# PowerSupply.net
KiCad netlist of a schematic drawn in Altium Designer
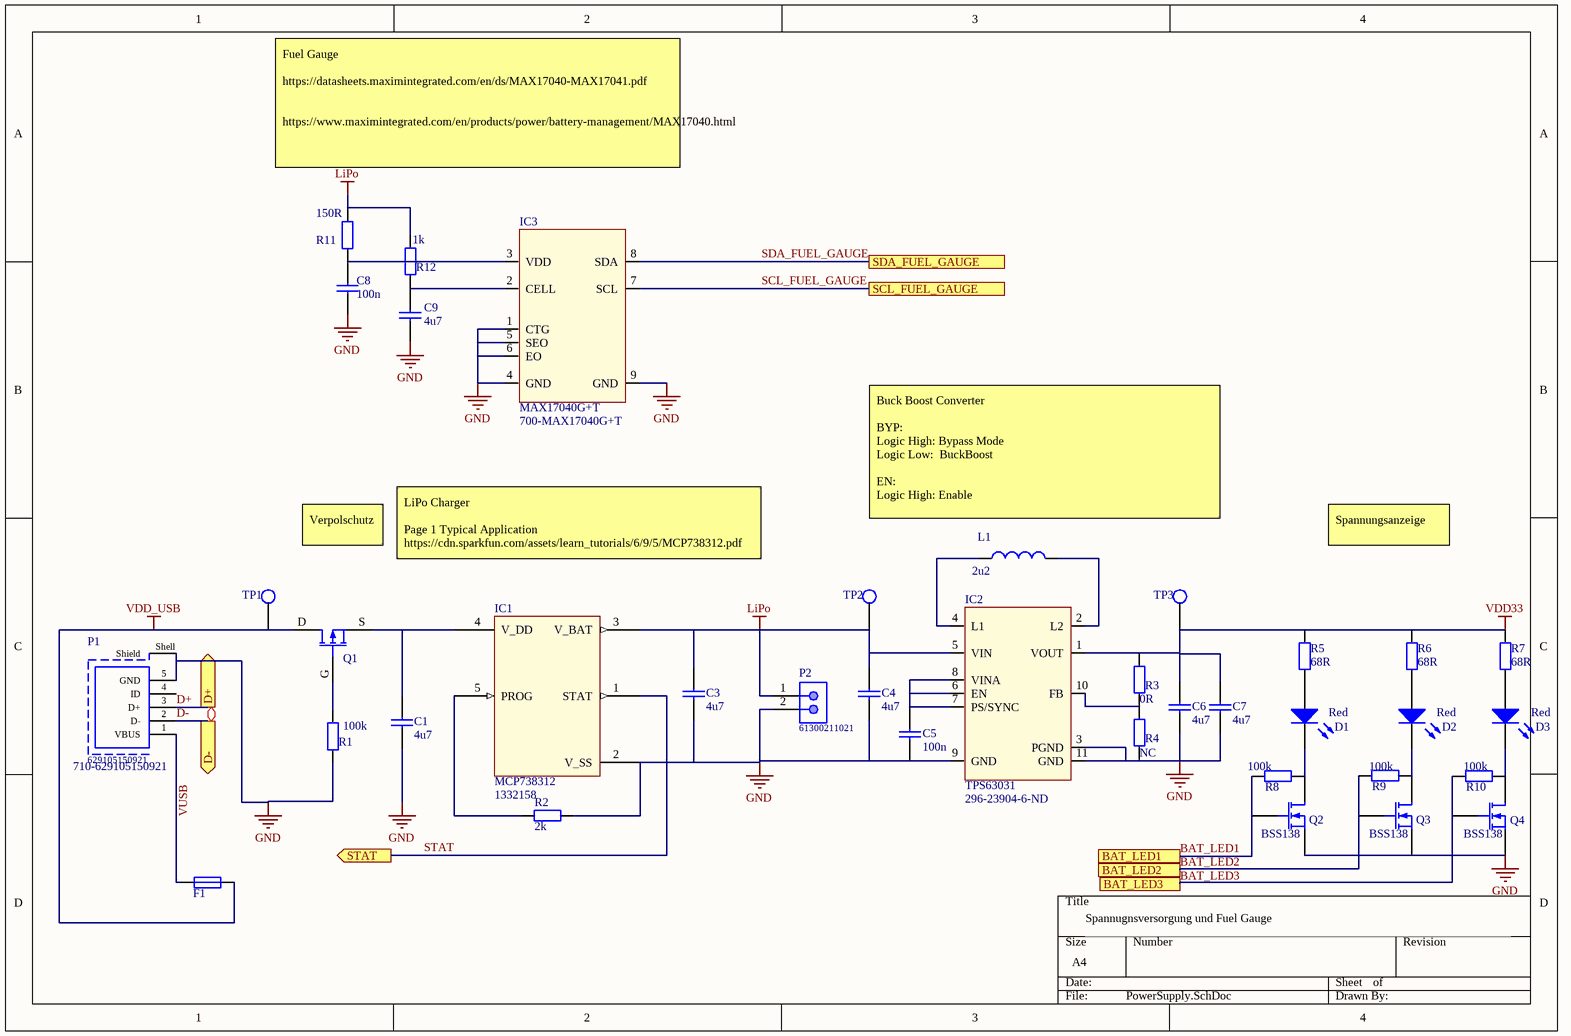
[diagram p0: PowerSupply.SchDoc]

(export (version "E")
  (design (tool "Eeschema 10.0.6"))
  (components
    (comp (ref "C1")
      (value "4u7")
      (footprint "CAPC1005X55")
      (description "Ceramic Chip Capacitor")
      (fields (field (name "MANUFACTURER") "TDK") (field (name "VOLTAGE") "10V"))
      (libsource (lib "SCT_MySQL_5.1") (part "Capacitor"))
    )
    (comp (ref "C3")
      (value "4u7")
      (footprint "CAPC1005X55")
      (description "Ceramic Chip Capacitor")
      (fields (field (name "MANUFACTURER") "Murata") (field (name "VOLTAGE") "6.3V"))
      (libsource (lib "SCT_MySQL_5.1") (part "Capacitor"))
    )
    (comp (ref "C4")
      (value "4u7")
      (footprint "CAPC1005X55")
      (description "Ceramic Chip Capacitor")
      (fields (field (name "MANUFACTURER") "Murata") (field (name "VOLTAGE") "6.3V"))
      (libsource (lib "SCT_MySQL_5.1") (part "Capacitor"))
    )
    (comp (ref "C5")
      (value "100n")
      (footprint "CAPC1005X55")
      (fields
        (field (name "MANUFACTURER") "Kemet")
        (field (name "VOLTAGE") "16V")
        (field (name "TOLERANCE") "±15%")
      )
      (libsource (lib "SCT_MySQL_5.1") (part "Capacitor"))
    )
    (comp (ref "C6")
      (value "4u7")
      (footprint "CAPC1005X55")
      (description "Ceramic Chip Capacitor")
      (fields (field (name "MANUFACTURER") "Murata") (field (name "VOLTAGE") "6.3V"))
      (libsource (lib "SCT_MySQL_5.1") (part "Capacitor"))
    )
    (comp (ref "C7")
      (value "4u7")
      (footprint "CAPC1005X55")
      (description "Ceramic Chip Capacitor")
      (fields (field (name "MANUFACTURER") "Murata") (field (name "VOLTAGE") "6.3V"))
      (libsource (lib "SCT_MySQL_5.1") (part "Capacitor"))
    )
    (comp (ref "C8")
      (value "100n")
      (footprint "CAPC1005X55")
      (description "Ceramic Chip Capacitor")
      (fields (field (name "MANUFACTURER") "Kemet") (field (name "VOLTAGE") "16V"))
      (libsource (lib "SCT_MySQL_5.1") (part "Capacitor"))
    )
    (comp (ref "C9")
      (value "4u7")
      (footprint "CAPC1005X55")
      (description "Ceramic Chip Capacitor")
      (fields (field (name "MANUFACTURER") "TDK") (field (name "VOLTAGE") "10V"))
      (libsource (lib "SCT_MySQL_5.1") (part "Capacitor"))
    )
    (comp (ref "D1")
      (value "Red")
      (footprint "LEDC2012X90")
      (description "SMD Chip LED")
      (fields (field (name "MANUFACTURER") "Avago"))
      (libsource (lib "SCT_MySQL_5.1") (part "LED"))
    )
    (comp (ref "D2")
      (value "Red")
      (footprint "LEDC2012X90")
      (description "SMD Chip LED")
      (fields (field (name "MANUFACTURER") "Avago"))
      (libsource (lib "SCT_MySQL_5.1") (part "LED"))
    )
    (comp (ref "D3")
      (value "Red")
      (footprint "LEDC2012X90")
      (description "SMD Chip LED")
      (fields (field (name "MANUFACTURER") "Avago"))
      (libsource (lib "SCT_MySQL_5.1") (part "LED"))
    )
    (comp (ref "F1")
      (value "~")
      (footprint "RESC3216X65")
      (description "0.5A PTC Fuse")
      (fields (field (name "MANUFACTURER") "POLY-FUSE"))
      (libsource (lib "SCT_MySQL_5.1") (part "Fuse"))
    )
    (comp (ref "IC1")
      (value "MCP738312")
      (footprint "MCP738312")
      (fields (field (name "SUPPLIER PART NUMBER 1") "1332158"))
      (libsource (lib "Lib") (part "MCP738312"))
    )
    (comp (ref "IC2")
      (value "TPS63031")
      (footprint "TPS63031")
      (fields (field (name "SUPPLIER PART NUMBER 1") "296-23904-6-ND"))
      (libsource (lib "Lib") (part "TPS63031"))
    )
    (comp (ref "IC3")
      (value "MAX17040G+T")
      (footprint "MAX17040G+T")
      (fields (field (name "SUPPLIER PART NUMBER 1") "700-MAX17040G+T"))
      (libsource (lib "Lib") (part "MAX17040G+T"))
    )
    (comp (ref "L1")
      (value "2u2")
      (footprint "INDM3030X150")
      (description "SMD Inductor")
      (fields (field (name "MANUFACTURER") "Taiyo Yuden") (field (name "TOLERANCE") "± 20%"))
      (libsource (lib "SCT_MySQL_5.1") (part "Inductor (Coil)"))
    )
    (comp (ref "P1")
      (value "629105150921")
      (footprint "629105150921")
      (description "Micro USB 2.0 Type AB Receptacle WR-COM, Horizontal, SMT")
      (fields
        (field (name "SUPPLIER PART NUMBER 1") "710-629105150921")
        (field (name "PUBLISHER") "Wurth Elektronik")
      )
      (libsource (lib "USB Connectors WR-USB") (part "629105150921"))
    )
    (comp (ref "P2")
      (value "61300211021")
      (footprint "61300211021")
      (description "THT Angled Pin Header WR-PHD, Pitch 2.54 mm, Single Row, 2 pins")
      (fields (field (name "PUBLISHER") "Wurth Elektronik"))
      (libsource (lib "ALTIUM-PHD_2_54_THT_ANGLED_PIN_HEADER_6130XX11021-rev18b (1)") (part "61300211021"))
    )
    (comp (ref "Q1")
      (value "IRLML9301TRPBF")
      (footprint "SOT95P240X130_SGD-3")
      (description "P-channel enhancement mode MOS transistor")
      (fields (field (name "MANUFACTURER") "International Rectifier"))
      (libsource (lib "SCT_MySQL_5.1") (part "MOSFET_P"))
    )
    (comp (ref "Q2")
      (value "BSS138")
      (footprint "SOT95P240X130_SGD-3")
      (description "N-channel enhancement mode MOS transistor")
      (fields (field (name "MANUFACTURER") "Infineon"))
      (libsource (lib "SCT_MySQL_5.1") (part "MOSFET_N"))
    )
    (comp (ref "Q3")
      (value "BSS138")
      (footprint "SOT95P240X130_SGD-3")
      (description "N-channel enhancement mode MOS transistor")
      (fields (field (name "MANUFACTURER") "Infineon"))
      (libsource (lib "SCT_MySQL_5.1") (part "MOSFET_N"))
    )
    (comp (ref "Q4")
      (value "BSS138")
      (footprint "SOT95P240X130_SGD-3")
      (description "N-channel enhancement mode MOS transistor")
      (fields (field (name "MANUFACTURER") "Infineon"))
      (libsource (lib "SCT_MySQL_5.1") (part "MOSFET_N"))
    )
    (comp (ref "R1")
      (value "100k")
      (footprint "RESC1005X40")
      (description "Resistor")
      (fields (field (name "MANUFACTURER") "Multicomp") (field (name "TOLERANCE") "±1%"))
      (libsource (lib "SCT_MySQL_5.1") (part "Resistor"))
    )
    (comp (ref "R2")
      (value "2k")
      (footprint "RESC1005X40")
      (description "Resistor")
      (fields (field (name "MANUFACTURER") "Multicomp") (field (name "TOLERANCE") "±1%"))
      (libsource (lib "") (part "Resistor_2"))
    )
    (comp (ref "R3")
      (value "0R")
      (footprint "RESC1005X40")
      (description "Resistor")
      (fields (field (name "MANUFACTURER") "Multicomp") (field (name "TOLERANCE") "±1%"))
      (libsource (lib "SCT_MySQL_5.1") (part "Resistor"))
    )
    (comp (ref "R4")
      (value "NC")
      (footprint "RESC1005X40")
      (description "Resistor")
      (fields (field (name "MANUFACTURER") "Multicomp") (field (name "TOLERANCE") "±1%"))
      (libsource (lib "SCT_MySQL_5.1") (part "Resistor"))
    )
    (comp (ref "R5")
      (value "68R")
      (footprint "RESC1005X40")
      (description "Resistor")
      (fields (field (name "MANUFACTURER") "Multicomp") (field (name "TOLERANCE") "±1%"))
      (libsource (lib "SCT_MySQL_5.1") (part "Resistor"))
    )
    (comp (ref "R6")
      (value "68R")
      (footprint "RESC1005X40")
      (description "Resistor")
      (fields (field (name "MANUFACTURER") "Multicomp") (field (name "TOLERANCE") "±1%"))
      (libsource (lib "SCT_MySQL_5.1") (part "Resistor"))
    )
    (comp (ref "R7")
      (value "68R")
      (footprint "RESC1005X40")
      (description "Resistor")
      (fields (field (name "MANUFACTURER") "Multicomp") (field (name "TOLERANCE") "±1%"))
      (libsource (lib "SCT_MySQL_5.1") (part "Resistor"))
    )
    (comp (ref "R8")
      (value "100k")
      (footprint "RESC1005X40")
      (description "Resistor")
      (fields (field (name "MANUFACTURER") "Multicomp") (field (name "TOLERANCE") "±1%"))
      (libsource (lib "") (part "Resistor_1"))
    )
    (comp (ref "R9")
      (value "100k")
      (footprint "RESC1005X40")
      (description "Resistor")
      (fields (field (name "MANUFACTURER") "Multicomp") (field (name "TOLERANCE") "±1%"))
      (libsource (lib "") (part "Resistor_1"))
    )
    (comp (ref "R10")
      (value "100k")
      (footprint "RESC1005X40")
      (description "Resistor")
      (fields (field (name "MANUFACTURER") "Multicomp") (field (name "TOLERANCE") "±1%"))
      (libsource (lib "") (part "Resistor_1"))
    )
    (comp (ref "R11")
      (value "150R")
      (footprint "RESC1005X40")
      (description "Resistor")
      (fields (field (name "MANUFACTURER") "Multicomp") (field (name "TOLERANCE") "±1%"))
      (libsource (lib "SCT_MySQL_5.1") (part "Resistor"))
    )
    (comp (ref "R12")
      (value "1k")
      (footprint "RESC1005X40")
      (description "Resistor")
      (fields (field (name "MANUFACTURER") "Multicomp") (field (name "TOLERANCE") "±1%"))
      (libsource (lib "SCT_MySQL_5.1") (part "Resistor"))
    )
    (comp (ref "TP1")
      (value "Testpoint")
      (footprint "TP200A")
      (description "Testpoint 2mm")
      (libsource (lib "SCT_MySQL_5.1") (part "Testpoint"))
    )
    (comp (ref "TP2")
      (value "Testpoint")
      (footprint "TP200A")
      (description "Testpoint 2mm")
      (libsource (lib "SCT_MySQL_5.1") (part "Testpoint"))
    )
    (comp (ref "TP3")
      (value "Testpoint")
      (footprint "TP200A")
      (description "Testpoint 2mm")
      (libsource (lib "SCT_MySQL_5.1") (part "Testpoint"))
    )
  )
  (nets
    (net (code "1") (name "/BAT_LED1") (class "Default")
      (node (ref "Q2") (pin "G") (pinfunction "G_G") (pintype "passive"))
      (node (ref "R8") (pin "1") (pinfunction "1_1") (pintype "passive"))
    )
    (net (code "2") (name "/BAT_LED2") (class "Default")
      (node (ref "Q3") (pin "G") (pinfunction "G_G") (pintype "passive"))
      (node (ref "R9") (pin "1") (pinfunction "1_1") (pintype "passive"))
    )
    (net (code "3") (name "/BAT_LED3") (class "Default")
      (node (ref "Q4") (pin "G") (pinfunction "G_G") (pintype "passive"))
      (node (ref "R10") (pin "1") (pinfunction "1_1") (pintype "passive"))
    )
    (net (code "4") (name "/D+") (class "Default")
      (node (ref "P1") (pin "3") (pinfunction "D+_3") (pintype "passive"))
    )
    (net (code "5") (name "/D-") (class "Default")
      (node (ref "P1") (pin "2") (pinfunction "D-_2") (pintype "passive"))
    )
    (net (code "6") (name "/SCL_FUEL_GAUGE") (class "Default")
      (node (ref "IC3") (pin "7") (pinfunction "SCL_7") (pintype "bidirectional"))
    )
    (net (code "7") (name "/SDA_FUEL_GAUGE") (class "Default")
      (node (ref "IC3") (pin "8") (pinfunction "SDA_8") (pintype "bidirectional"))
    )
    (net (code "8") (name "/STAT") (class "Default")
      (node (ref "IC1") (pin "1") (pinfunction "STAT_1") (pintype "output"))
    )
    (net (code "10") (name "GND") (class "Default")
      (node (ref "C1") (pin "1") (pinfunction "1_1") (pintype "passive"))
      (node (ref "C3") (pin "1") (pinfunction "1_1") (pintype "passive"))
      (node (ref "C4") (pin "1") (pinfunction "1_1") (pintype "passive"))
      (node (ref "C5") (pin "2") (pinfunction "2_2") (pintype "passive"))
      (node (ref "C6") (pin "1") (pinfunction "1_1") (pintype "passive"))
      (node (ref "C7") (pin "1") (pinfunction "1_1") (pintype "passive"))
      (node (ref "C8") (pin "1") (pinfunction "1_1") (pintype "passive"))
      (node (ref "C9") (pin "1") (pinfunction "1_1") (pintype "passive"))
      (node (ref "IC1") (pin "2") (pinfunction "V_SS_2") (pintype "passive"))
      (node (ref "IC2") (pin "11") (pinfunction "GND_11") (pintype "passive"))
      (node (ref "IC2") (pin "3") (pinfunction "PGND_3") (pintype "passive"))
      (node (ref "IC2") (pin "9") (pinfunction "GND_9") (pintype "passive"))
      (node (ref "IC3") (pin "1") (pinfunction "CTG_1") (pintype "passive"))
      (node (ref "IC3") (pin "4") (pinfunction "GND_4") (pintype "passive"))
      (node (ref "IC3") (pin "5") (pinfunction "SEO_5") (pintype "passive"))
      (node (ref "IC3") (pin "6") (pinfunction "EO_6") (pintype "passive"))
      (node (ref "IC3") (pin "9") (pinfunction "GND_9") (pintype "passive"))
      (node (ref "P1") (pin "5") (pinfunction "GND_5") (pintype "passive"))
      (node (ref "P1") (pin "Shell") (pinfunction "Shield_Shell") (pintype "passive"))
      (node (ref "P2") (pin "2") (pinfunction "2_2") (pintype "passive"))
      (node (ref "Q2") (pin "S") (pinfunction "S_S") (pintype "passive"))
      (node (ref "Q3") (pin "S") (pinfunction "S_S") (pintype "passive"))
      (node (ref "Q4") (pin "S") (pinfunction "S_S") (pintype "passive"))
      (node (ref "R1") (pin "1") (pinfunction "1_1") (pintype "passive"))
      (node (ref "R2") (pin "1") (pinfunction "1_1") (pintype "passive"))
      (node (ref "R4") (pin "1") (pinfunction "1_1") (pintype "passive"))
    )
    (net (code "11") (name "LiPo") (class "Default")
      (node (ref "C3") (pin "2") (pinfunction "2_2") (pintype "passive"))
      (node (ref "C4") (pin "2") (pinfunction "2_2") (pintype "passive"))
      (node (ref "IC1") (pin "3") (pinfunction "V_BAT_3") (pintype "output"))
      (node (ref "IC2") (pin "5") (pinfunction "VIN_5") (pintype "passive"))
      (node (ref "P2") (pin "1") (pinfunction "1_1") (pintype "passive"))
      (node (ref "R11") (pin "2") (pinfunction "2_2") (pintype "passive"))
      (node (ref "R12") (pin "2") (pinfunction "2_2") (pintype "passive"))
      (node (ref "TP2") (pin "1") (pinfunction "1_1") (pintype "passive"))
    )
    (net (code "12") (name "Net-(D1-A)") (class "Default")
      (node (ref "D1") (pin "2") (pinfunction "A_2") (pintype "passive"))
      (node (ref "R5") (pin "1") (pinfunction "1_1") (pintype "passive"))
    )
    (net (code "13") (name "Net-(D1-K)") (class "Default")
      (node (ref "D1") (pin "1") (pinfunction "K_1") (pintype "passive"))
      (node (ref "Q2") (pin "D") (pinfunction "D_D") (pintype "passive"))
      (node (ref "R8") (pin "2") (pinfunction "2_2") (pintype "passive"))
    )
    (net (code "14") (name "Net-(D2-A)") (class "Default")
      (node (ref "D2") (pin "2") (pinfunction "A_2") (pintype "passive"))
      (node (ref "R6") (pin "1") (pinfunction "1_1") (pintype "passive"))
    )
    (net (code "15") (name "Net-(D2-K)") (class "Default")
      (node (ref "D2") (pin "1") (pinfunction "K_1") (pintype "passive"))
      (node (ref "Q3") (pin "D") (pinfunction "D_D") (pintype "passive"))
      (node (ref "R9") (pin "2") (pinfunction "2_2") (pintype "passive"))
    )
    (net (code "16") (name "Net-(D3-A)") (class "Default")
      (node (ref "D3") (pin "2") (pinfunction "A_2") (pintype "passive"))
      (node (ref "R7") (pin "1") (pinfunction "1_1") (pintype "passive"))
    )
    (net (code "17") (name "Net-(D3-K)") (class "Default")
      (node (ref "D3") (pin "1") (pinfunction "K_1") (pintype "passive"))
      (node (ref "Q4") (pin "D") (pinfunction "D_D") (pintype "passive"))
      (node (ref "R10") (pin "2") (pinfunction "2_2") (pintype "passive"))
    )
    (net (code "18") (name "Net-(IC1-PROG)") (class "Default")
      (node (ref "IC1") (pin "5") (pinfunction "PROG_5") (pintype "input"))
      (node (ref "R2") (pin "2") (pinfunction "2_2") (pintype "passive"))
    )
    (net (code "19") (name "Net-(IC1-V_DD)") (class "Default")
      (node (ref "C1") (pin "2") (pinfunction "2_2") (pintype "passive"))
      (node (ref "IC1") (pin "4") (pinfunction "V_DD_4") (pintype "power_in"))
      (node (ref "Q1") (pin "S") (pinfunction "S_S") (pintype "passive"))
    )
    (net (code "20") (name "Net-(IC2-EN)") (class "Default")
      (node (ref "C5") (pin "1") (pinfunction "1_1") (pintype "passive"))
      (node (ref "IC2") (pin "6") (pinfunction "EN_6") (pintype "passive"))
      (node (ref "IC2") (pin "7") (pinfunction "PS/SYNC_7") (pintype "passive"))
      (node (ref "IC2") (pin "8") (pinfunction "VINA_8") (pintype "passive"))
    )
    (net (code "21") (name "Net-(IC2-FB)") (class "Default")
      (node (ref "IC2") (pin "10") (pinfunction "FB_10") (pintype "passive"))
      (node (ref "R3") (pin "1") (pinfunction "1_1") (pintype "passive"))
      (node (ref "R4") (pin "2") (pinfunction "2_2") (pintype "passive"))
    )
    (net (code "22") (name "Net-(IC2-L1)") (class "Default")
      (node (ref "IC2") (pin "4") (pinfunction "L1_4") (pintype "passive"))
      (node (ref "L1") (pin "1") (pinfunction "1_1") (pintype "passive"))
    )
    (net (code "23") (name "Net-(IC2-L2)") (class "Default")
      (node (ref "IC2") (pin "2") (pinfunction "L2_2") (pintype "passive"))
      (node (ref "L1") (pin "2") (pinfunction "2_2") (pintype "passive"))
    )
    (net (code "24") (name "Net-(IC3-CELL)") (class "Default")
      (node (ref "C9") (pin "2") (pinfunction "2_2") (pintype "passive"))
      (node (ref "IC3") (pin "2") (pinfunction "CELL_2") (pintype "passive"))
      (node (ref "R12") (pin "1") (pinfunction "1_1") (pintype "passive"))
    )
    (net (code "25") (name "Net-(IC3-VDD)") (class "Default")
      (node (ref "C8") (pin "2") (pinfunction "2_2") (pintype "passive"))
      (node (ref "IC3") (pin "3") (pinfunction "VDD_3") (pintype "passive"))
      (node (ref "R11") (pin "1") (pinfunction "1_1") (pintype "passive"))
    )
    (net (code "26") (name "Net-(P1-VBUS)") (class "Default")
      (node (ref "F1") (pin "1") (pinfunction "1_1") (pintype "passive"))
      (node (ref "P1") (pin "1") (pinfunction "VBUS_1") (pintype "passive"))
    )
    (net (code "27") (name "Net-(Q1-PadG)") (class "Default")
      (node (ref "Q1") (pin "G") (pinfunction "G_G") (pintype "passive"))
      (node (ref "R1") (pin "2") (pinfunction "2_2") (pintype "passive"))
    )
    (net (code "28") (name "VDD33") (class "Default")
      (node (ref "C6") (pin "2") (pinfunction "2_2") (pintype "passive"))
      (node (ref "C7") (pin "2") (pinfunction "2_2") (pintype "passive"))
      (node (ref "IC2") (pin "1") (pinfunction "VOUT_1") (pintype "passive"))
      (node (ref "R3") (pin "2") (pinfunction "2_2") (pintype "passive"))
      (node (ref "R5") (pin "2") (pinfunction "2_2") (pintype "passive"))
      (node (ref "R6") (pin "2") (pinfunction "2_2") (pintype "passive"))
      (node (ref "R7") (pin "2") (pinfunction "2_2") (pintype "passive"))
      (node (ref "TP3") (pin "1") (pinfunction "1_1") (pintype "passive"))
    )
    (net (code "29") (name "VDD_USB") (class "Default")
      (node (ref "F1") (pin "2") (pinfunction "2_2") (pintype "passive"))
      (node (ref "Q1") (pin "D") (pinfunction "D_D") (pintype "passive"))
      (node (ref "TP1") (pin "1") (pinfunction "1_1") (pintype "passive"))
    )
    (net (code "30") (name "unconnected-(P1-ID-Pad4)") (class "Default")
      (node (ref "P1") (pin "4") (pinfunction "ID_4") (pintype "passive"))
    )
  )
)
